# pcb3.net
KiCad netlist of a schematic drawn in EAGLE
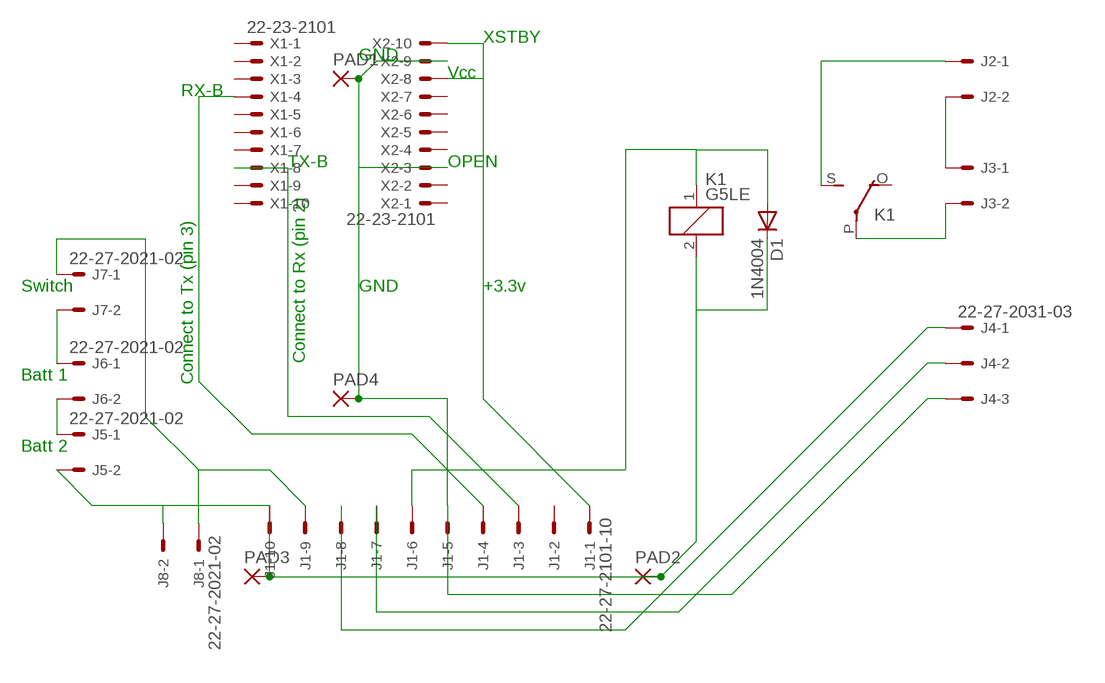
[diagram p0: schematic, sheet 1]

(export (version "E")
  (design (tool "Eeschema 10.0.6"))
  (components
    (comp (ref "D1")
      (value "1N4004")
      (footprint "eagle-import:DO41-10")
      (libsource (lib "eagle-import") (part "1N4004"))
    )
    (comp (ref "J1")
      (value "22-27-2101-10")
      (footprint "eagle-import:6410-10")
      (libsource (lib "eagle-import") (part "22-?-1027-2101"))
    )
    (comp (ref "J2")
      (value "KK-156-2")
      (footprint "eagle-import:KK-156-2")
      (libsource (lib "eagle-import") (part "KK-156-2"))
    )
    (comp (ref "J3")
      (value "KK-156-2")
      (footprint "eagle-import:KK-156-2")
      (libsource (lib "eagle-import") (part "KK-156-2"))
    )
    (comp (ref "J4")
      (value "22-27-2031-03")
      (footprint "eagle-import:6410-03")
      (libsource (lib "eagle-import") (part "22-?-0327-2031"))
    )
    (comp (ref "J5")
      (value "22-27-2021-02")
      (footprint "eagle-import:6410-02")
      (libsource (lib "eagle-import") (part "22-?-0227-2021"))
    )
    (comp (ref "J6")
      (value "22-27-2021-02")
      (footprint "eagle-import:6410-02")
      (libsource (lib "eagle-import") (part "22-?-0227-2021"))
    )
    (comp (ref "J7")
      (value "22-27-2021-02")
      (footprint "eagle-import:6410-02")
      (libsource (lib "eagle-import") (part "22-?-0227-2021"))
    )
    (comp (ref "J8")
      (value "22-27-2021-02")
      (footprint "eagle-import:6410-02")
      (libsource (lib "eagle-import") (part "22-?-0227-2021"))
    )
    (comp (ref "K1")
      (value "G5LE")
      (footprint "eagle-import:G5LE")
      (libsource (lib "eagle-import") (part "G5LE"))
    )
    (comp (ref "PAD1")
      (value "1,6/0,8")
      (footprint "eagle-import:1,6_0,8")
      (libsource (lib "eagle-import") (part "1,6/0,8"))
    )
    (comp (ref "PAD2")
      (value "1,6/0,8")
      (footprint "eagle-import:1,6_0,8")
      (libsource (lib "eagle-import") (part "1,6/0,8"))
    )
    (comp (ref "PAD3")
      (value "1,6/0,8")
      (footprint "eagle-import:1,6_0,8")
      (libsource (lib "eagle-import") (part "1,6/0,8"))
    )
    (comp (ref "PAD4")
      (value "1,6/0,8")
      (footprint "eagle-import:1,6_0,8")
      (libsource (lib "eagle-import") (part "1,6/0,8"))
    )
    (comp (ref "X1")
      (value "22-23-2101")
      (footprint "eagle-import:22-23-2101")
      (fields (field (name "MF") "MOLEX"))
      (libsource (lib "eagle-import") (part "22-23-2101"))
    )
    (comp (ref "X2")
      (value "22-23-2101")
      (footprint "eagle-import:22-23-2101")
      (fields (field (name "MF") "MOLEX"))
      (libsource (lib "eagle-import") (part "22-23-2101"))
    )
  )
  (nets
    (net (code "1") (name "Net-(J1A-S)") (class "Default")
      (node (ref "J1") (pin "1") (pinfunction "S_1") (pintype "passive"))
      (node (ref "X2") (pin "10") (pinfunction "S_10") (pintype "passive"))
      (node (ref "X2") (pin "8") (pinfunction "S_8") (pintype "passive"))
    )
    (net (code "2") (name "Net-(J1B-S)") (class "Default")
      (node (ref "D1") (pin "C") (pinfunction "C_C") (pintype "passive"))
      (node (ref "J1") (pin "10") (pinfunction "S_10") (pintype "passive"))
      (node (ref "J5") (pin "2") (pinfunction "S_2") (pintype "passive"))
      (node (ref "J8") (pin "2") (pinfunction "S_2") (pintype "passive"))
      (node (ref "K1") (pin "2") (pinfunction "2_2") (pintype "passive"))
      (node (ref "PAD2") (pin "1") (pinfunction "P_1") (pintype "passive"))
      (node (ref "PAD3") (pin "1") (pinfunction "P_1") (pintype "passive"))
    )
    (net (code "3") (name "Net-(J1D-S)") (class "Default")
      (node (ref "J1") (pin "3") (pinfunction "S_3") (pintype "passive"))
      (node (ref "X1") (pin "8") (pinfunction "S_8") (pintype "passive"))
    )
    (net (code "4") (name "Net-(J1E-S)") (class "Default")
      (node (ref "J1") (pin "4") (pinfunction "S_4") (pintype "passive"))
      (node (ref "X1") (pin "4") (pinfunction "S_4") (pintype "passive"))
    )
    (net (code "5") (name "Net-(J1F-S)") (class "Default")
      (node (ref "J1") (pin "5") (pinfunction "S_5") (pintype "passive"))
      (node (ref "J4") (pin "3") (pinfunction "S_3") (pintype "passive"))
      (node (ref "PAD1") (pin "1") (pinfunction "P_1") (pintype "passive"))
      (node (ref "PAD4") (pin "1") (pinfunction "P_1") (pintype "passive"))
      (node (ref "X2") (pin "3") (pinfunction "S_3") (pintype "passive"))
      (node (ref "X2") (pin "9") (pinfunction "S_9") (pintype "passive"))
    )
    (net (code "6") (name "Net-(J1G-S)") (class "Default")
      (node (ref "D1") (pin "A") (pinfunction "A_A") (pintype "passive"))
      (node (ref "J1") (pin "6") (pinfunction "S_6") (pintype "passive"))
      (node (ref "K1") (pin "1") (pinfunction "1_1") (pintype "passive"))
    )
    (net (code "7") (name "Net-(J1H-S)") (class "Default")
      (node (ref "J1") (pin "7") (pinfunction "S_7") (pintype "passive"))
      (node (ref "J4") (pin "2") (pinfunction "S_2") (pintype "passive"))
    )
    (net (code "8") (name "Net-(J1I-S)") (class "Default")
      (node (ref "J1") (pin "8") (pinfunction "S_8") (pintype "passive"))
      (node (ref "J4") (pin "1") (pinfunction "S_1") (pintype "passive"))
    )
    (net (code "9") (name "Net-(J1J-S)") (class "Default")
      (node (ref "J1") (pin "9") (pinfunction "S_9") (pintype "passive"))
      (node (ref "J7") (pin "1") (pinfunction "S_1") (pintype "passive"))
      (node (ref "J8") (pin "1") (pinfunction "S_1") (pintype "passive"))
    )
    (net (code "10") (name "Net-(J2A-S)") (class "Default")
      (node (ref "J2") (pin "1") (pinfunction "S_1") (pintype "passive"))
      (node (ref "K1") (pin "S") (pinfunction "S_S") (pintype "passive"))
    )
    (net (code "11") (name "Net-(J2B-S)") (class "Default")
      (node (ref "J2") (pin "2") (pinfunction "S_2") (pintype "passive"))
      (node (ref "J3") (pin "1") (pinfunction "S_1") (pintype "passive"))
    )
    (net (code "12") (name "Net-(J3B-S)") (class "Default")
      (node (ref "J3") (pin "2") (pinfunction "S_2") (pintype "passive"))
      (node (ref "K1") (pin "P") (pinfunction "P_P") (pintype "passive"))
    )
    (net (code "13") (name "Net-(J5A-S)") (class "Default")
      (node (ref "J5") (pin "1") (pinfunction "S_1") (pintype "passive"))
      (node (ref "J6") (pin "2") (pinfunction "S_2") (pintype "passive"))
    )
    (net (code "14") (name "Net-(J6A-S)") (class "Default")
      (node (ref "J6") (pin "1") (pinfunction "S_1") (pintype "passive"))
      (node (ref "J7") (pin "2") (pinfunction "S_2") (pintype "passive"))
    )
    (net (code "15") (name "unconnected-(J1C-S-Pad2)") (class "Default")
      (node (ref "J1") (pin "2") (pinfunction "S_2") (pintype "passive"))
    )
    (net (code "16") (name "unconnected-(K1-PadO)") (class "Default")
      (node (ref "K1") (pin "O") (pinfunction "O_O") (pintype "passive"))
    )
    (net (code "17") (name "unconnected-(X1A-S-Pad1)") (class "Default")
      (node (ref "X1") (pin "1") (pinfunction "S_1") (pintype "passive"))
    )
    (net (code "18") (name "unconnected-(X1B-S-Pad10)") (class "Default")
      (node (ref "X1") (pin "10") (pinfunction "S_10") (pintype "passive"))
    )
    (net (code "19") (name "unconnected-(X1C-S-Pad2)") (class "Default")
      (node (ref "X1") (pin "2") (pinfunction "S_2") (pintype "passive"))
    )
    (net (code "20") (name "unconnected-(X1D-S-Pad3)") (class "Default")
      (node (ref "X1") (pin "3") (pinfunction "S_3") (pintype "passive"))
    )
    (net (code "21") (name "unconnected-(X1F-S-Pad5)") (class "Default")
      (node (ref "X1") (pin "5") (pinfunction "S_5") (pintype "passive"))
    )
    (net (code "22") (name "unconnected-(X1G-S-Pad6)") (class "Default")
      (node (ref "X1") (pin "6") (pinfunction "S_6") (pintype "passive"))
    )
    (net (code "23") (name "unconnected-(X1H-S-Pad7)") (class "Default")
      (node (ref "X1") (pin "7") (pinfunction "S_7") (pintype "passive"))
    )
    (net (code "24") (name "unconnected-(X1J-S-Pad9)") (class "Default")
      (node (ref "X1") (pin "9") (pinfunction "S_9") (pintype "passive"))
    )
    (net (code "25") (name "unconnected-(X2A-S-Pad1)") (class "Default")
      (node (ref "X2") (pin "1") (pinfunction "S_1") (pintype "passive"))
    )
    (net (code "26") (name "unconnected-(X2C-S-Pad2)") (class "Default")
      (node (ref "X2") (pin "2") (pinfunction "S_2") (pintype "passive"))
    )
    (net (code "27") (name "unconnected-(X2E-S-Pad4)") (class "Default")
      (node (ref "X2") (pin "4") (pinfunction "S_4") (pintype "passive"))
    )
    (net (code "28") (name "unconnected-(X2F-S-Pad5)") (class "Default")
      (node (ref "X2") (pin "5") (pinfunction "S_5") (pintype "passive"))
    )
    (net (code "29") (name "unconnected-(X2G-S-Pad6)") (class "Default")
      (node (ref "X2") (pin "6") (pinfunction "S_6") (pintype "passive"))
    )
    (net (code "30") (name "unconnected-(X2H-S-Pad7)") (class "Default")
      (node (ref "X2") (pin "7") (pinfunction "S_7") (pintype "passive"))
    )
  )
)
